# distribution_board.net
KiCad netlist of a schematic drawn in EAGLE
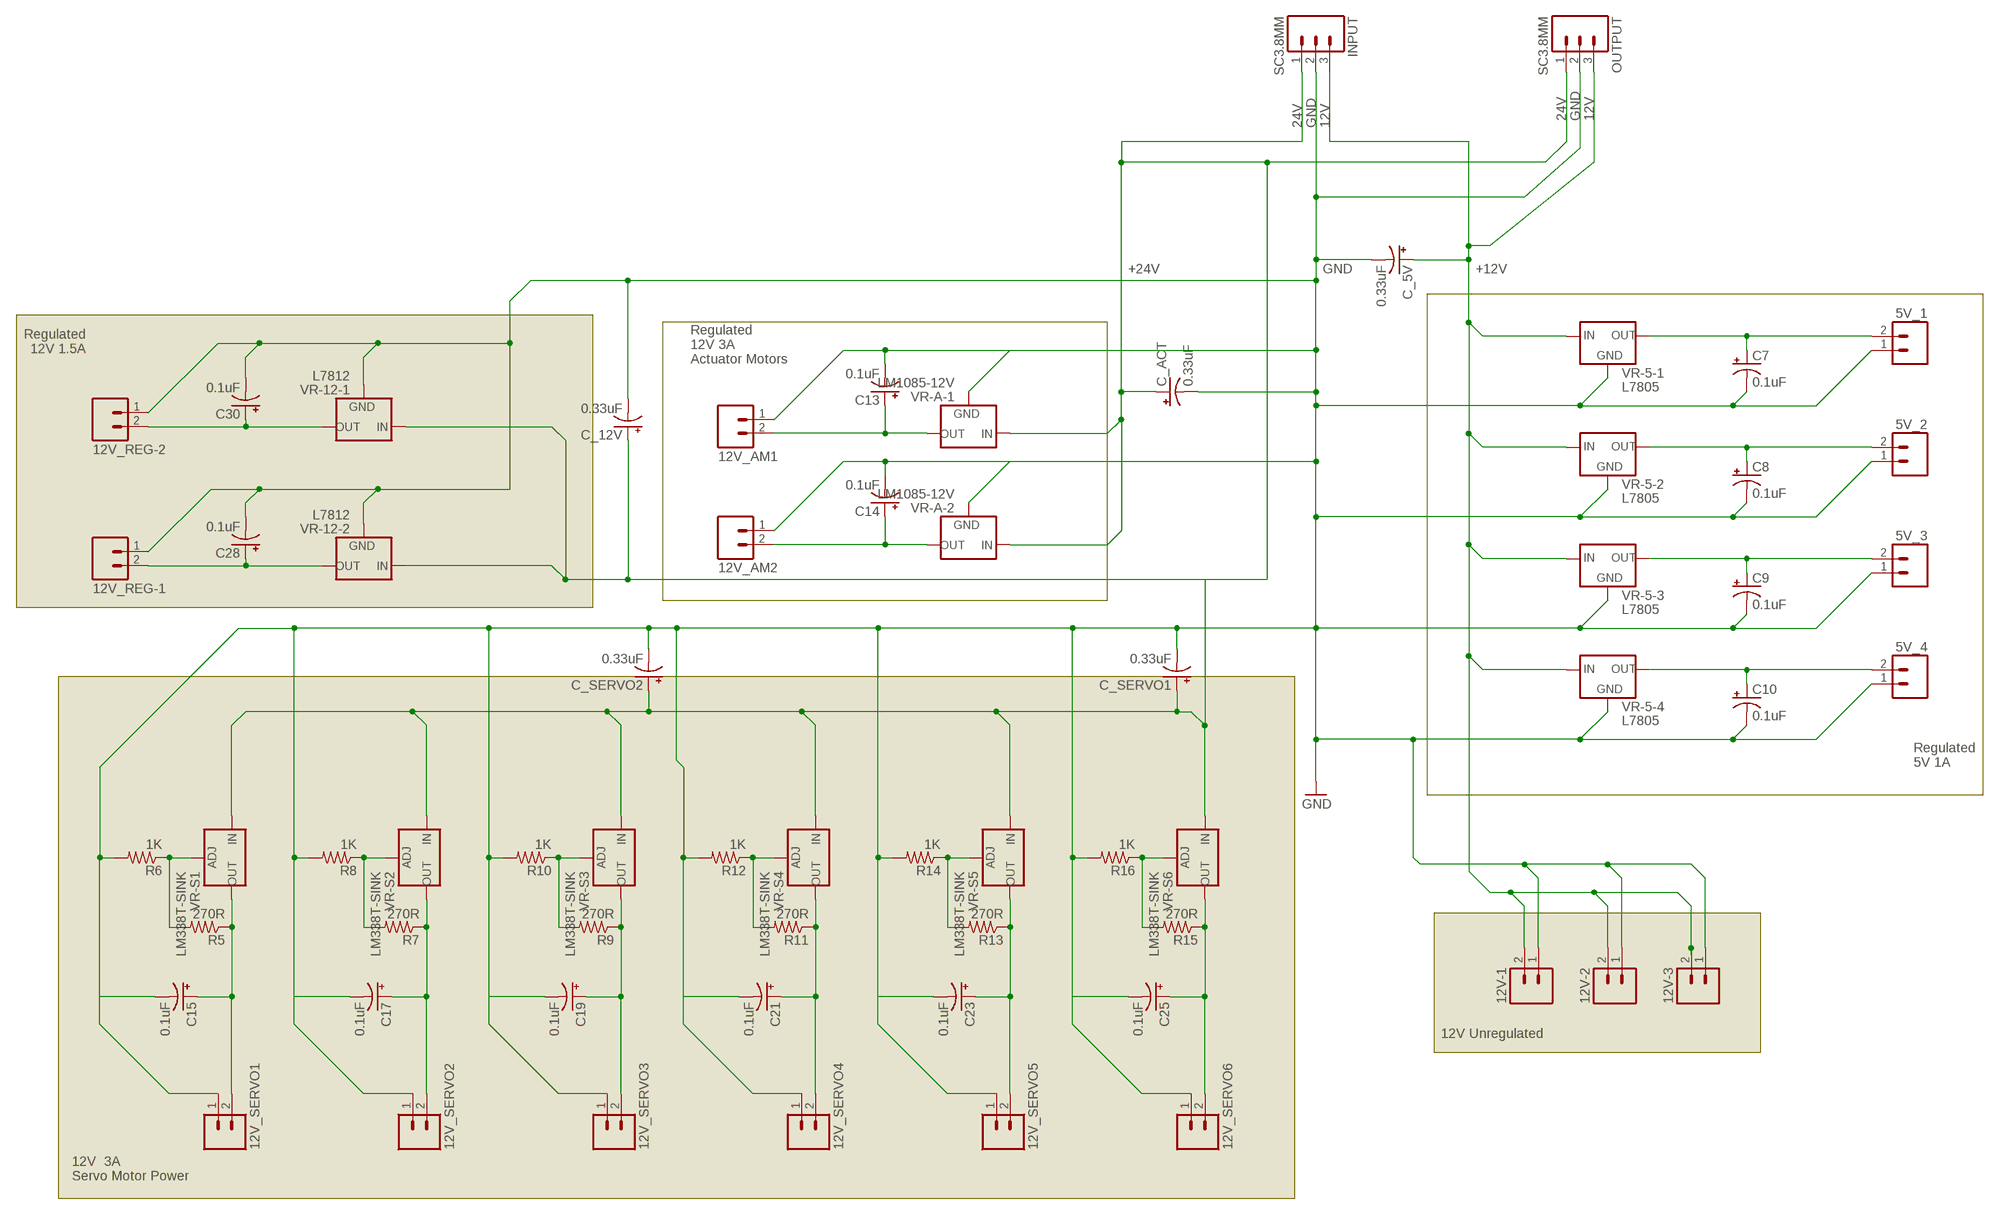
[diagram p0: schematic, sheet 1]

(export (version "E")
  (design (tool "Eeschema 10.0.6"))
  (components
    (comp (ref "5V_1")
      (value "SC3.81MM")
      (footprint "eagle-import:SCREWTERMINAL-3.81MM")
      (libsource (lib "eagle-import") (part "2-HOLESSC3.81MM"))
    )
    (comp (ref "5V_2")
      (value "SC3.81MM")
      (footprint "eagle-import:SCREWTERMINAL-3.81MM")
      (libsource (lib "eagle-import") (part "2-HOLESSC3.81MM"))
    )
    (comp (ref "5V_3")
      (value "SC3.81MM")
      (footprint "eagle-import:SCREWTERMINAL-3.81MM")
      (libsource (lib "eagle-import") (part "2-HOLESSC3.81MM"))
    )
    (comp (ref "5V_4")
      (value "SC3.81MM")
      (footprint "eagle-import:SCREWTERMINAL-3.81MM")
      (libsource (lib "eagle-import") (part "2-HOLESSC3.81MM"))
    )
    (comp (ref "12V-1")
      (value "SC3.81MM")
      (footprint "eagle-import:SCREWTERMINAL-3.81MM")
      (libsource (lib "eagle-import") (part "2-HOLESSC3.81MM"))
    )
    (comp (ref "12V-2")
      (value "SC3.81MM")
      (footprint "eagle-import:SCREWTERMINAL-3.81MM")
      (libsource (lib "eagle-import") (part "2-HOLESSC3.81MM"))
    )
    (comp (ref "12V-3")
      (value "SC3.81MM")
      (footprint "eagle-import:SCREWTERMINAL-3.81MM")
      (libsource (lib "eagle-import") (part "2-HOLESSC3.81MM"))
    )
    (comp (ref "12V_AM1")
      (value "SC3.81MM")
      (footprint "eagle-import:SCREWTERMINAL-3.81MM")
      (libsource (lib "eagle-import") (part "2-HOLESSC3.81MM"))
    )
    (comp (ref "12V_AM2")
      (value "SC3.81MM")
      (footprint "eagle-import:SCREWTERMINAL-3.81MM")
      (libsource (lib "eagle-import") (part "2-HOLESSC3.81MM"))
    )
    (comp (ref "12V_REG-1")
      (value "SC3.81MM")
      (footprint "eagle-import:SCREWTERMINAL-3.81MM")
      (libsource (lib "eagle-import") (part "2-HOLESSC3.81MM"))
    )
    (comp (ref "12V_REG-2")
      (value "SC3.81MM")
      (footprint "eagle-import:SCREWTERMINAL-3.81MM")
      (libsource (lib "eagle-import") (part "2-HOLESSC3.81MM"))
    )
    (comp (ref "12V_SERVO1")
      (value "SC3.81MM")
      (footprint "eagle-import:SCREWTERMINAL-3.81MM")
      (libsource (lib "eagle-import") (part "2-HOLESSC3.81MM"))
    )
    (comp (ref "12V_SERVO2")
      (value "SC3.81MM")
      (footprint "eagle-import:SCREWTERMINAL-3.81MM")
      (libsource (lib "eagle-import") (part "2-HOLESSC3.81MM"))
    )
    (comp (ref "12V_SERVO3")
      (value "SC3.81MM")
      (footprint "eagle-import:SCREWTERMINAL-3.81MM")
      (libsource (lib "eagle-import") (part "2-HOLESSC3.81MM"))
    )
    (comp (ref "12V_SERVO4")
      (value "SC3.81MM")
      (footprint "eagle-import:SCREWTERMINAL-3.81MM")
      (libsource (lib "eagle-import") (part "2-HOLESSC3.81MM"))
    )
    (comp (ref "12V_SERVO5")
      (value "SC3.81MM")
      (footprint "eagle-import:SCREWTERMINAL-3.81MM")
      (libsource (lib "eagle-import") (part "2-HOLESSC3.81MM"))
    )
    (comp (ref "12V_SERVO6")
      (value "SC3.81MM")
      (footprint "eagle-import:SCREWTERMINAL-3.81MM")
      (libsource (lib "eagle-import") (part "2-HOLESSC3.81MM"))
    )
    (comp (ref "C7")
      (value "0.1uF")
      (footprint "eagle-import:E2,5-5")
      (libsource (lib "eagle-import") (part "CAPACITOR_POL"))
    )
    (comp (ref "C8")
      (value "0.1uF")
      (footprint "eagle-import:E2,5-5")
      (libsource (lib "eagle-import") (part "CAPACITOR_POL"))
    )
    (comp (ref "C9")
      (value "0.1uF")
      (footprint "eagle-import:E2,5-5")
      (libsource (lib "eagle-import") (part "CAPACITOR_POL"))
    )
    (comp (ref "C10")
      (value "0.1uF")
      (footprint "eagle-import:E2,5-5")
      (libsource (lib "eagle-import") (part "CAPACITOR_POL"))
    )
    (comp (ref "C13")
      (value "0.1uF")
      (footprint "eagle-import:E2,5-5")
      (libsource (lib "eagle-import") (part "CAPACITOR_POL"))
    )
    (comp (ref "C14")
      (value "0.1uF")
      (footprint "eagle-import:E2,5-5")
      (libsource (lib "eagle-import") (part "CAPACITOR_POL"))
    )
    (comp (ref "C15")
      (value "0.1uF")
      (footprint "eagle-import:E2,5-5")
      (libsource (lib "eagle-import") (part "CAPACITOR_POL"))
    )
    (comp (ref "C17")
      (value "0.1uF")
      (footprint "eagle-import:E2,5-5")
      (libsource (lib "eagle-import") (part "CAPACITOR_POL"))
    )
    (comp (ref "C19")
      (value "0.1uF")
      (footprint "eagle-import:E2,5-5")
      (libsource (lib "eagle-import") (part "CAPACITOR_POL"))
    )
    (comp (ref "C21")
      (value "0.1uF")
      (footprint "eagle-import:E2,5-5")
      (libsource (lib "eagle-import") (part "CAPACITOR_POL"))
    )
    (comp (ref "C23")
      (value "0.1uF")
      (footprint "eagle-import:E2,5-5")
      (libsource (lib "eagle-import") (part "CAPACITOR_POL"))
    )
    (comp (ref "C25")
      (value "0.1uF")
      (footprint "eagle-import:E2,5-5")
      (libsource (lib "eagle-import") (part "CAPACITOR_POL"))
    )
    (comp (ref "C28")
      (value "0.1uF")
      (footprint "eagle-import:E2,5-5")
      (libsource (lib "eagle-import") (part "CAPACITOR_POL"))
    )
    (comp (ref "C30")
      (value "0.1uF")
      (footprint "eagle-import:E2,5-5")
      (libsource (lib "eagle-import") (part "CAPACITOR_POL"))
    )
    (comp (ref "C_5V")
      (value "0.33uF")
      (footprint "eagle-import:E2,5-5")
      (libsource (lib "eagle-import") (part "CAPACITOR_POL"))
    )
    (comp (ref "C_12V")
      (value "0.33uF")
      (footprint "eagle-import:E2,5-5")
      (libsource (lib "eagle-import") (part "CAPACITOR_POL"))
    )
    (comp (ref "C_ACT")
      (value "0.33uF")
      (footprint "eagle-import:E2,5-5")
      (libsource (lib "eagle-import") (part "CAPACITOR_POL"))
    )
    (comp (ref "C_SERVO1")
      (value "0.33uF")
      (footprint "eagle-import:E2,5-5")
      (libsource (lib "eagle-import") (part "CAPACITOR_POL"))
    )
    (comp (ref "C_SERVO2")
      (value "0.33uF")
      (footprint "eagle-import:E2,5-5")
      (libsource (lib "eagle-import") (part "CAPACITOR_POL"))
    )
    (comp (ref "INPUT")
      (value "SC3.8MM")
      (footprint "eagle-import:SCREWTERMINAL-5MM-3")
      (libsource (lib "eagle-import") (part "3-HOLES"))
    )
    (comp (ref "OUTPUT")
      (value "SC3.8MM")
      (footprint "eagle-import:SCREWTERMINAL-5MM-3")
      (libsource (lib "eagle-import") (part "3-HOLES"))
    )
    (comp (ref "R5")
      (value "270R")
      (footprint "eagle-import:0207_2V")
      (libsource (lib "eagle-import") (part "RESISTOR0207/2V"))
    )
    (comp (ref "R6")
      (value "1K")
      (footprint "eagle-import:0207_2V")
      (libsource (lib "eagle-import") (part "RESISTOR0207/2V"))
    )
    (comp (ref "R7")
      (value "270R")
      (footprint "eagle-import:0207_2V")
      (libsource (lib "eagle-import") (part "RESISTOR0207/2V"))
    )
    (comp (ref "R8")
      (value "1K")
      (footprint "eagle-import:0207_2V")
      (libsource (lib "eagle-import") (part "RESISTOR0207/2V"))
    )
    (comp (ref "R9")
      (value "270R")
      (footprint "eagle-import:0207_2V")
      (libsource (lib "eagle-import") (part "RESISTOR0207/2V"))
    )
    (comp (ref "R10")
      (value "1K")
      (footprint "eagle-import:0207_2V")
      (libsource (lib "eagle-import") (part "RESISTOR0207/2V"))
    )
    (comp (ref "R11")
      (value "270R")
      (footprint "eagle-import:0207_2V")
      (libsource (lib "eagle-import") (part "RESISTOR0207/2V"))
    )
    (comp (ref "R12")
      (value "1K")
      (footprint "eagle-import:0207_2V")
      (libsource (lib "eagle-import") (part "RESISTOR0207/2V"))
    )
    (comp (ref "R13")
      (value "270R")
      (footprint "eagle-import:0207_2V")
      (libsource (lib "eagle-import") (part "RESISTOR0207/2V"))
    )
    (comp (ref "R14")
      (value "1K")
      (footprint "eagle-import:0207_2V")
      (libsource (lib "eagle-import") (part "RESISTOR0207/2V"))
    )
    (comp (ref "R15")
      (value "270R")
      (footprint "eagle-import:0207_2V")
      (libsource (lib "eagle-import") (part "RESISTOR0207/2V"))
    )
    (comp (ref "R16")
      (value "1K")
      (footprint "eagle-import:0207_2V")
      (libsource (lib "eagle-import") (part "RESISTOR0207/2V"))
    )
    (comp (ref "VR-5-1")
      (value "L7805")
      (footprint "eagle-import:TO263")
      (libsource (lib "eagle-import") (part "L7805ACD2T-TR"))
    )
    (comp (ref "VR-5-2")
      (value "L7805")
      (footprint "eagle-import:TO263")
      (libsource (lib "eagle-import") (part "L7805ACD2T-TR"))
    )
    (comp (ref "VR-5-3")
      (value "L7805")
      (footprint "eagle-import:TO263")
      (libsource (lib "eagle-import") (part "L7805ACD2T-TR"))
    )
    (comp (ref "VR-5-4")
      (value "L7805")
      (footprint "eagle-import:TO263")
      (libsource (lib "eagle-import") (part "L7805ACD2T-TR"))
    )
    (comp (ref "VR-12-1")
      (value "L7812")
      (footprint "eagle-import:TO263")
      (libsource (lib "eagle-import") (part "L7812CD2T-TRTO-263"))
    )
    (comp (ref "VR-12-2")
      (value "L7812")
      (footprint "eagle-import:TO263")
      (libsource (lib "eagle-import") (part "L7812CD2T-TRTO-263"))
    )
    (comp (ref "VR-A-1")
      (value "LM1085-12V")
      (footprint "eagle-import:TO220V-HEATSINK")
      (libsource (lib "eagle-import") (part "LM1085IT-SINK"))
    )
    (comp (ref "VR-A-2")
      (value "LM1085-12V")
      (footprint "eagle-import:TO220V-HEATSINK")
      (libsource (lib "eagle-import") (part "LM1085IT-SINK"))
    )
    (comp (ref "VR-S1")
      (value "LM338T-SINK")
      (footprint "eagle-import:TO220V-HEATSINK")
      (libsource (lib "eagle-import") (part "LM338T-SINK"))
    )
    (comp (ref "VR-S2")
      (value "LM338T-SINK")
      (footprint "eagle-import:TO220V-HEATSINK")
      (libsource (lib "eagle-import") (part "LM338T-SINK"))
    )
    (comp (ref "VR-S3")
      (value "LM338T-SINK")
      (footprint "eagle-import:TO220V-HEATSINK")
      (libsource (lib "eagle-import") (part "LM338T-SINK"))
    )
    (comp (ref "VR-S4")
      (value "LM338T-SINK")
      (footprint "eagle-import:TO220V-HEATSINK")
      (libsource (lib "eagle-import") (part "LM338T-SINK"))
    )
    (comp (ref "VR-S5")
      (value "LM338T-SINK")
      (footprint "eagle-import:TO220V-HEATSINK")
      (libsource (lib "eagle-import") (part "LM338T-SINK"))
    )
    (comp (ref "VR-S6")
      (value "LM338T-SINK")
      (footprint "eagle-import:TO220V-HEATSINK")
      (libsource (lib "eagle-import") (part "LM338T-SINK"))
    )
  )
  (nets
    (net (code "1") (name "/12V") (class "Default")
      (node (ref "12V-1") (pin "2") (pinfunction "2_2") (pintype "passive"))
      (node (ref "12V-2") (pin "2") (pinfunction "2_2") (pintype "passive"))
      (node (ref "12V-3") (pin "2") (pinfunction "2_2") (pintype "passive"))
      (node (ref "C_5V") (pin "+") (pinfunction "+_+") (pintype "passive"))
      (node (ref "INPUT") (pin "3") (pinfunction "3_3") (pintype "passive"))
      (node (ref "OUTPUT") (pin "3") (pinfunction "3_3") (pintype "passive"))
      (node (ref "VR-5-1") (pin "1") (pinfunction "IN_1") (pintype "input"))
      (node (ref "VR-5-2") (pin "1") (pinfunction "IN_1") (pintype "input"))
      (node (ref "VR-5-3") (pin "1") (pinfunction "IN_1") (pintype "input"))
      (node (ref "VR-5-4") (pin "1") (pinfunction "IN_1") (pintype "input"))
    )
    (net (code "2") (name "/24V") (class "Default")
      (node (ref "C_12V") (pin "+") (pinfunction "+_+") (pintype "passive"))
      (node (ref "C_ACT") (pin "+") (pinfunction "+_+") (pintype "passive"))
      (node (ref "C_SERVO1") (pin "+") (pinfunction "+_+") (pintype "passive"))
      (node (ref "C_SERVO2") (pin "+") (pinfunction "+_+") (pintype "passive"))
      (node (ref "INPUT") (pin "1") (pinfunction "1_1") (pintype "passive"))
      (node (ref "OUTPUT") (pin "1") (pinfunction "1_1") (pintype "passive"))
      (node (ref "VR-12-1") (pin "1") (pinfunction "IN_1") (pintype "input"))
      (node (ref "VR-12-2") (pin "1") (pinfunction "IN_1") (pintype "input"))
      (node (ref "VR-A-1") (pin "3") (pinfunction "IN_3") (pintype "input"))
      (node (ref "VR-A-2") (pin "3") (pinfunction "IN_3") (pintype "input"))
      (node (ref "VR-S1") (pin "3") (pinfunction "IN_3") (pintype "input"))
      (node (ref "VR-S2") (pin "3") (pinfunction "IN_3") (pintype "input"))
      (node (ref "VR-S3") (pin "3") (pinfunction "IN_3") (pintype "input"))
      (node (ref "VR-S4") (pin "3") (pinfunction "IN_3") (pintype "input"))
      (node (ref "VR-S5") (pin "3") (pinfunction "IN_3") (pintype "input"))
      (node (ref "VR-S6") (pin "3") (pinfunction "IN_3") (pintype "input"))
    )
    (net (code "3") (name "GND") (class "Default")
      (node (ref "12V-1") (pin "1") (pinfunction "1_1") (pintype "passive"))
      (node (ref "12V-2") (pin "1") (pinfunction "1_1") (pintype "passive"))
      (node (ref "12V-3") (pin "1") (pinfunction "1_1") (pintype "passive"))
      (node (ref "12V_AM1") (pin "1") (pinfunction "1_1") (pintype "passive"))
      (node (ref "12V_AM2") (pin "1") (pinfunction "1_1") (pintype "passive"))
      (node (ref "12V_REG-1") (pin "1") (pinfunction "1_1") (pintype "passive"))
      (node (ref "12V_REG-2") (pin "1") (pinfunction "1_1") (pintype "passive"))
      (node (ref "12V_SERVO1") (pin "1") (pinfunction "1_1") (pintype "passive"))
      (node (ref "12V_SERVO2") (pin "1") (pinfunction "1_1") (pintype "passive"))
      (node (ref "12V_SERVO3") (pin "1") (pinfunction "1_1") (pintype "passive"))
      (node (ref "12V_SERVO4") (pin "1") (pinfunction "1_1") (pintype "passive"))
      (node (ref "12V_SERVO5") (pin "1") (pinfunction "1_1") (pintype "passive"))
      (node (ref "12V_SERVO6") (pin "1") (pinfunction "1_1") (pintype "passive"))
      (node (ref "5V_1") (pin "1") (pinfunction "1_1") (pintype "passive"))
      (node (ref "5V_2") (pin "1") (pinfunction "1_1") (pintype "passive"))
      (node (ref "5V_3") (pin "1") (pinfunction "1_1") (pintype "passive"))
      (node (ref "5V_4") (pin "1") (pinfunction "1_1") (pintype "passive"))
      (node (ref "C10") (pin "-") (pinfunction "-_-") (pintype "passive"))
      (node (ref "C13") (pin "-") (pinfunction "-_-") (pintype "passive"))
      (node (ref "C14") (pin "-") (pinfunction "-_-") (pintype "passive"))
      (node (ref "C15") (pin "-") (pinfunction "-_-") (pintype "passive"))
      (node (ref "C17") (pin "-") (pinfunction "-_-") (pintype "passive"))
      (node (ref "C19") (pin "-") (pinfunction "-_-") (pintype "passive"))
      (node (ref "C21") (pin "-") (pinfunction "-_-") (pintype "passive"))
      (node (ref "C23") (pin "-") (pinfunction "-_-") (pintype "passive"))
      (node (ref "C25") (pin "-") (pinfunction "-_-") (pintype "passive"))
      (node (ref "C28") (pin "-") (pinfunction "-_-") (pintype "passive"))
      (node (ref "C30") (pin "-") (pinfunction "-_-") (pintype "passive"))
      (node (ref "C7") (pin "-") (pinfunction "-_-") (pintype "passive"))
      (node (ref "C8") (pin "-") (pinfunction "-_-") (pintype "passive"))
      (node (ref "C9") (pin "-") (pinfunction "-_-") (pintype "passive"))
      (node (ref "C_12V") (pin "-") (pinfunction "-_-") (pintype "passive"))
      (node (ref "C_5V") (pin "-") (pinfunction "-_-") (pintype "passive"))
      (node (ref "C_ACT") (pin "-") (pinfunction "-_-") (pintype "passive"))
      (node (ref "C_SERVO1") (pin "-") (pinfunction "-_-") (pintype "passive"))
      (node (ref "C_SERVO2") (pin "-") (pinfunction "-_-") (pintype "passive"))
      (node (ref "INPUT") (pin "2") (pinfunction "2_2") (pintype "passive"))
      (node (ref "OUTPUT") (pin "2") (pinfunction "2_2") (pintype "passive"))
      (node (ref "R10") (pin "2") (pinfunction "2_2") (pintype "passive"))
      (node (ref "R12") (pin "2") (pinfunction "2_2") (pintype "passive"))
      (node (ref "R14") (pin "2") (pinfunction "2_2") (pintype "passive"))
      (node (ref "R16") (pin "2") (pinfunction "2_2") (pintype "passive"))
      (node (ref "R6") (pin "2") (pinfunction "2_2") (pintype "passive"))
      (node (ref "R8") (pin "2") (pinfunction "2_2") (pintype "passive"))
      (node (ref "VR-12-1") (pin "3") (pinfunction "GND_3") (pintype "input"))
      (node (ref "VR-12-2") (pin "3") (pinfunction "GND_3") (pintype "input"))
      (node (ref "VR-5-1") (pin "3") (pinfunction "GND_3") (pintype "input"))
      (node (ref "VR-5-2") (pin "3") (pinfunction "GND_3") (pintype "input"))
      (node (ref "VR-5-3") (pin "3") (pinfunction "GND_3") (pintype "input"))
      (node (ref "VR-5-4") (pin "3") (pinfunction "GND_3") (pintype "input"))
      (node (ref "VR-A-1") (pin "1") (pinfunction "GND_1") (pintype "input"))
      (node (ref "VR-A-2") (pin "1") (pinfunction "GND_1") (pintype "input"))
    )
    (net (code "4") (name "Net-(VR-5-1-OUT)") (class "Default")
      (node (ref "5V_1") (pin "2") (pinfunction "2_2") (pintype "passive"))
      (node (ref "C7") (pin "+") (pinfunction "+_+") (pintype "passive"))
      (node (ref "VR-5-1") (pin "2") (pinfunction "OUT_2") (pintype "passive"))
    )
    (net (code "5") (name "Net-(VR-5-2-OUT)") (class "Default")
      (node (ref "5V_2") (pin "2") (pinfunction "2_2") (pintype "passive"))
      (node (ref "C8") (pin "+") (pinfunction "+_+") (pintype "passive"))
      (node (ref "VR-5-2") (pin "2") (pinfunction "OUT_2") (pintype "passive"))
    )
    (net (code "6") (name "Net-(VR-5-3-OUT)") (class "Default")
      (node (ref "5V_3") (pin "2") (pinfunction "2_2") (pintype "passive"))
      (node (ref "C9") (pin "+") (pinfunction "+_+") (pintype "passive"))
      (node (ref "VR-5-3") (pin "2") (pinfunction "OUT_2") (pintype "passive"))
    )
    (net (code "7") (name "Net-(VR-5-4-OUT)") (class "Default")
      (node (ref "5V_4") (pin "2") (pinfunction "2_2") (pintype "passive"))
      (node (ref "C10") (pin "+") (pinfunction "+_+") (pintype "passive"))
      (node (ref "VR-5-4") (pin "2") (pinfunction "OUT_2") (pintype "passive"))
    )
    (net (code "8") (name "Net-(VR-12-1-OUT)") (class "Default")
      (node (ref "12V_REG-2") (pin "2") (pinfunction "2_2") (pintype "passive"))
      (node (ref "C30") (pin "+") (pinfunction "+_+") (pintype "passive"))
      (node (ref "VR-12-1") (pin "2") (pinfunction "OUT_2") (pintype "passive"))
    )
    (net (code "9") (name "Net-(VR-12-2-OUT)") (class "Default")
      (node (ref "12V_REG-1") (pin "2") (pinfunction "2_2") (pintype "passive"))
      (node (ref "C28") (pin "+") (pinfunction "+_+") (pintype "passive"))
      (node (ref "VR-12-2") (pin "2") (pinfunction "OUT_2") (pintype "passive"))
    )
    (net (code "10") (name "Net-(VR-A-1-OUT)") (class "Default")
      (node (ref "12V_AM1") (pin "2") (pinfunction "2_2") (pintype "passive"))
      (node (ref "C13") (pin "+") (pinfunction "+_+") (pintype "passive"))
      (node (ref "VR-A-1") (pin "2") (pinfunction "OUT_2") (pintype "passive"))
    )
    (net (code "11") (name "Net-(VR-A-2-OUT)") (class "Default")
      (node (ref "12V_AM2") (pin "2") (pinfunction "2_2") (pintype "passive"))
      (node (ref "C14") (pin "+") (pinfunction "+_+") (pintype "passive"))
      (node (ref "VR-A-2") (pin "2") (pinfunction "OUT_2") (pintype "passive"))
    )
    (net (code "12") (name "Net-(VR-S1-ADJ)") (class "Default")
      (node (ref "R5") (pin "2") (pinfunction "2_2") (pintype "passive"))
      (node (ref "R6") (pin "1") (pinfunction "1_1") (pintype "passive"))
      (node (ref "VR-S1") (pin "1") (pinfunction "ADJ_1") (pintype "input"))
    )
    (net (code "13") (name "Net-(VR-S1-OUT)") (class "Default")
      (node (ref "12V_SERVO1") (pin "2") (pinfunction "2_2") (pintype "passive"))
      (node (ref "C15") (pin "+") (pinfunction "+_+") (pintype "passive"))
      (node (ref "R5") (pin "1") (pinfunction "1_1") (pintype "passive"))
      (node (ref "VR-S1") (pin "2") (pinfunction "OUT_2") (pintype "passive"))
    )
    (net (code "14") (name "Net-(VR-S2-ADJ)") (class "Default")
      (node (ref "R7") (pin "2") (pinfunction "2_2") (pintype "passive"))
      (node (ref "R8") (pin "1") (pinfunction "1_1") (pintype "passive"))
      (node (ref "VR-S2") (pin "1") (pinfunction "ADJ_1") (pintype "input"))
    )
    (net (code "15") (name "Net-(VR-S2-OUT)") (class "Default")
      (node (ref "12V_SERVO2") (pin "2") (pinfunction "2_2") (pintype "passive"))
      (node (ref "C17") (pin "+") (pinfunction "+_+") (pintype "passive"))
      (node (ref "R7") (pin "1") (pinfunction "1_1") (pintype "passive"))
      (node (ref "VR-S2") (pin "2") (pinfunction "OUT_2") (pintype "passive"))
    )
    (net (code "16") (name "Net-(VR-S3-ADJ)") (class "Default")
      (node (ref "R10") (pin "1") (pinfunction "1_1") (pintype "passive"))
      (node (ref "R9") (pin "2") (pinfunction "2_2") (pintype "passive"))
      (node (ref "VR-S3") (pin "1") (pinfunction "ADJ_1") (pintype "input"))
    )
    (net (code "17") (name "Net-(VR-S3-OUT)") (class "Default")
      (node (ref "12V_SERVO3") (pin "2") (pinfunction "2_2") (pintype "passive"))
      (node (ref "C19") (pin "+") (pinfunction "+_+") (pintype "passive"))
      (node (ref "R9") (pin "1") (pinfunction "1_1") (pintype "passive"))
      (node (ref "VR-S3") (pin "2") (pinfunction "OUT_2") (pintype "passive"))
    )
    (net (code "18") (name "Net-(VR-S4-ADJ)") (class "Default")
      (node (ref "R11") (pin "2") (pinfunction "2_2") (pintype "passive"))
      (node (ref "R12") (pin "1") (pinfunction "1_1") (pintype "passive"))
      (node (ref "VR-S4") (pin "1") (pinfunction "ADJ_1") (pintype "input"))
    )
    (net (code "19") (name "Net-(VR-S4-OUT)") (class "Default")
      (node (ref "12V_SERVO4") (pin "2") (pinfunction "2_2") (pintype "passive"))
      (node (ref "C21") (pin "+") (pinfunction "+_+") (pintype "passive"))
      (node (ref "R11") (pin "1") (pinfunction "1_1") (pintype "passive"))
      (node (ref "VR-S4") (pin "2") (pinfunction "OUT_2") (pintype "passive"))
    )
    (net (code "20") (name "Net-(VR-S5-ADJ)") (class "Default")
      (node (ref "R13") (pin "2") (pinfunction "2_2") (pintype "passive"))
      (node (ref "R14") (pin "1") (pinfunction "1_1") (pintype "passive"))
      (node (ref "VR-S5") (pin "1") (pinfunction "ADJ_1") (pintype "input"))
    )
    (net (code "21") (name "Net-(VR-S5-OUT)") (class "Default")
      (node (ref "12V_SERVO5") (pin "2") (pinfunction "2_2") (pintype "passive"))
      (node (ref "C23") (pin "+") (pinfunction "+_+") (pintype "passive"))
      (node (ref "R13") (pin "1") (pinfunction "1_1") (pintype "passive"))
      (node (ref "VR-S5") (pin "2") (pinfunction "OUT_2") (pintype "passive"))
    )
    (net (code "22") (name "Net-(VR-S6-ADJ)") (class "Default")
      (node (ref "R15") (pin "2") (pinfunction "2_2") (pintype "passive"))
      (node (ref "R16") (pin "1") (pinfunction "1_1") (pintype "passive"))
      (node (ref "VR-S6") (pin "1") (pinfunction "ADJ_1") (pintype "input"))
    )
    (net (code "23") (name "Net-(VR-S6-OUT)") (class "Default")
      (node (ref "12V_SERVO6") (pin "2") (pinfunction "2_2") (pintype "passive"))
      (node (ref "C25") (pin "+") (pinfunction "+_+") (pintype "passive"))
      (node (ref "R15") (pin "1") (pinfunction "1_1") (pintype "passive"))
      (node (ref "VR-S6") (pin "2") (pinfunction "OUT_2") (pintype "passive"))
    )
  )
)
